# MCU_V3_1.net
KiCad netlist of a schematic drawn in Altium Designer
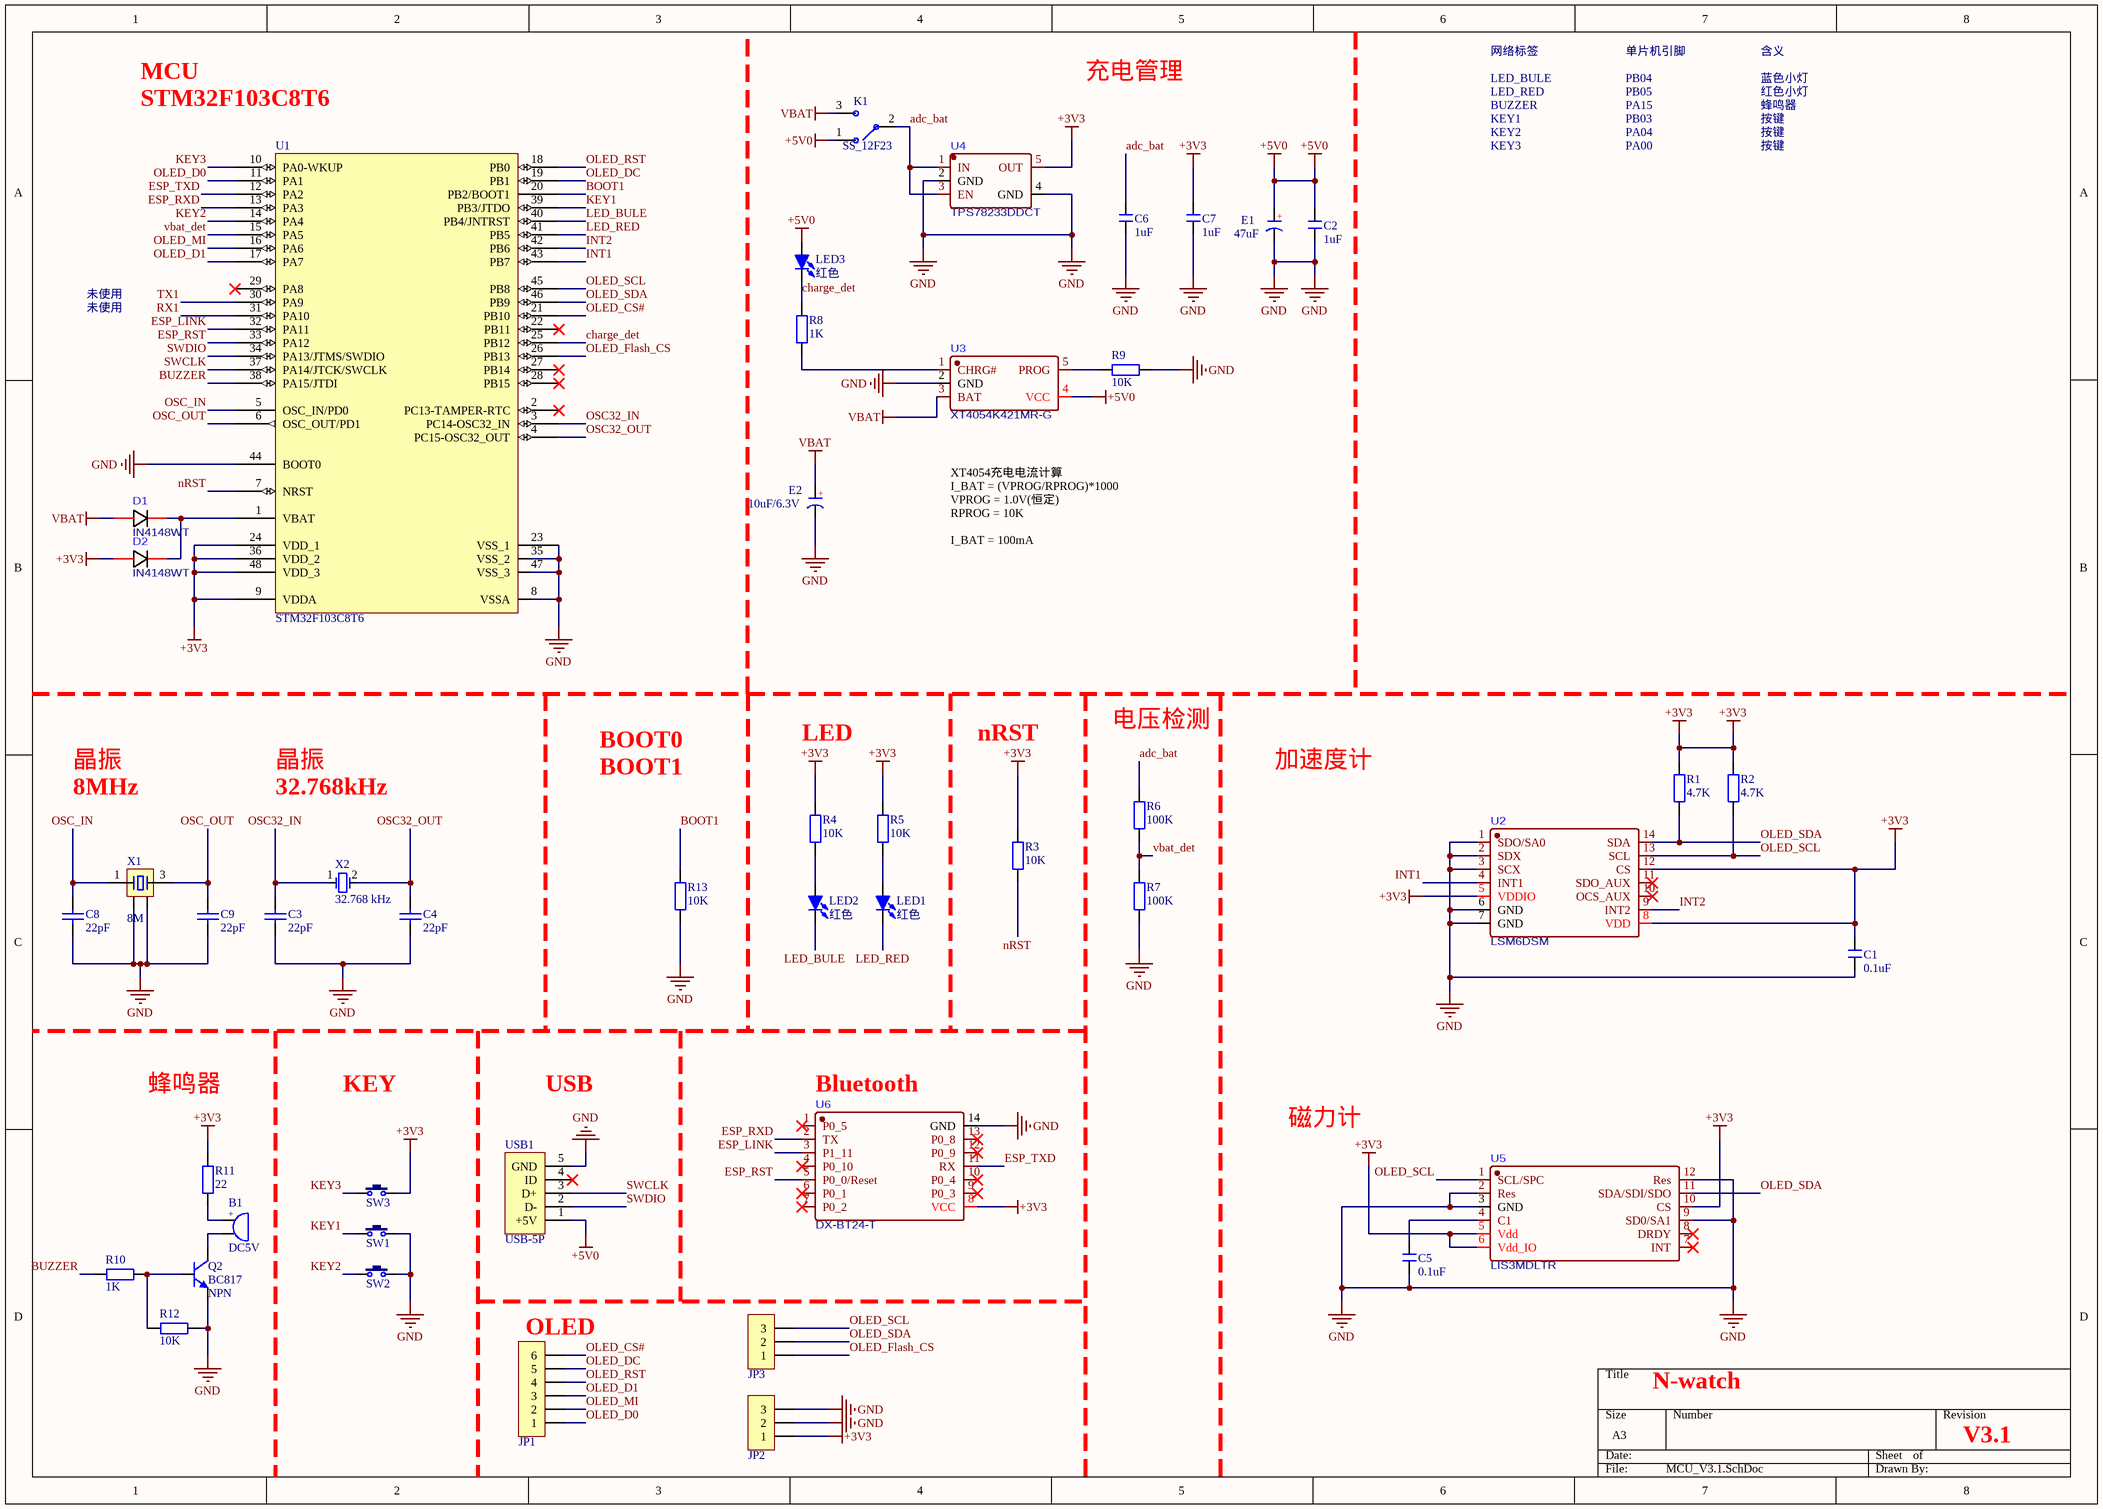
[diagram p0: MCU_V3.1.SchDoc]

(export (version "E")
  (design (tool "Eeschema 10.0.6"))
  (components
    (comp (ref "B1")
      (value "DC5V")
      (footprint "蜂鸣器5020")
      (description "蜂鸣器")
      (fields (field (name "版权归属") "黎明电子style"))
      (libsource (lib "未分类器件") (part "BEEP"))
    )
    (comp (ref "C1")
      (value "0.1uF")
      (footprint "C 0603")
      (description "无极性贴片电容")
      (fields (field (name "版权归属") "黎明电子style"))
      (libsource (lib "电阻-电容-电感") (part "C"))
    )
    (comp (ref "C2")
      (value "1uF")
      (footprint "C 0603")
      (description "无极性贴片电容")
      (fields (field (name "版权归属") "黎明电子style"))
      (libsource (lib "电阻-电容-电感") (part "C"))
    )
    (comp (ref "C3")
      (value "22pF")
      (footprint "C 0603")
      (description "贴片电容/MLCC电容")
      (libsource (lib "") (part "C_1"))
    )
    (comp (ref "C4")
      (value "22pF")
      (footprint "C 0603")
      (description "贴片电容/MLCC电容")
      (libsource (lib "") (part "C_1"))
    )
    (comp (ref "C5")
      (value "0.1uF")
      (footprint "C 0603")
      (description "无极性贴片电容")
      (fields (field (name "版权归属") "黎明电子style"))
      (libsource (lib "电阻-电容-电感") (part "C"))
    )
    (comp (ref "C6")
      (value "1uF")
      (footprint "C 0603")
      (description "无极性贴片电容")
      (fields (field (name "版权归属") "黎明电子style"))
      (libsource (lib "电阻-电容-电感") (part "C"))
    )
    (comp (ref "C7")
      (value "1uF")
      (footprint "C 0603")
      (description "无极性贴片电容")
      (fields (field (name "版权归属") "黎明电子style"))
      (libsource (lib "电阻-电容-电感") (part "C"))
    )
    (comp (ref "C8")
      (value "22pF")
      (footprint "C 0603")
      (description "贴片电容/MLCC电容")
      (libsource (lib "R-L-C-FUSE-XTAL-FB-RX") (part "C"))
    )
    (comp (ref "C9")
      (value "22pF")
      (footprint "C 0603")
      (description "贴片电容/MLCC电容")
      (libsource (lib "R-L-C-FUSE-XTAL-FB-RX") (part "C"))
    )
    (comp (ref "D1") (value "IN4148WT") (footprint "IN4148WT") (libsource (lib "Schlib1") (part "IN4148WT")))
    (comp (ref "D2") (value "IN4148WT") (footprint "IN4148WT") (libsource (lib "Schlib1") (part "IN4148WT")))
    (comp (ref "E1")
      (value "47uF")
      (footprint "CD A(3216)")
      (description "贴片钽电容")
      (fields (field (name "版权归属") "黎明电子style"))
      (libsource (lib "电阻-电容-电感") (part "C-CD"))
    )
    (comp (ref "E2")
      (value "10uF/6.3V")
      (footprint "CD A(3216)")
      (description "贴片钽电容")
      (fields (field (name "版权归属") "黎明电子style"))
      (libsource (lib "电阻-电容-电感") (part "C-CD"))
    )
    (comp (ref "JP1")
      (value "HDR-1X6")
      (footprint "HDR-1X6")
      (description "6P接插件")
      (fields (field (name "版权归属") "黎明电子style"))
      (libsource (lib "接插件") (part "Header 6"))
    )
    (comp (ref "JP2")
      (value "HDR-1X3")
      (footprint "OLED_3PIN")
      (description "3P接插件")
      (fields (field (name "版权归属") "黎明电子style"))
      (libsource (lib "接插件") (part "Header 3"))
    )
    (comp (ref "JP3")
      (value "HDR-1X3")
      (footprint "OLED_3PIN")
      (description "3P接插件")
      (fields (field (name "版权归属") "黎明电子style"))
      (libsource (lib "接插件") (part "Header 3"))
    )
    (comp (ref "K1") (value "SS_12F23") (footprint "SS_12F23") (libsource (lib "Schlib1") (part "SS_12F23")))
    (comp (ref "LED1")
      (value "红色")
      (footprint "LED 0603G")
      (description "贴片LED")
      (fields (field (name "版权归属") "黎明电子style"))
      (libsource (lib "LED") (part "LED-SMD"))
    )
    (comp (ref "LED2")
      (value "红色")
      (footprint "LED 0603G")
      (description "贴片LED")
      (fields (field (name "版权归属") "黎明电子style"))
      (libsource (lib "LED") (part "LED-SMD"))
    )
    (comp (ref "LED3")
      (value "红色")
      (footprint "LED 0603G")
      (description "贴片LED")
      (fields (field (name "版权归属") "黎明电子style"))
      (libsource (lib "LED") (part "LED-SMD"))
    )
    (comp (ref "Q2")
      (value "BC817")
      (footprint "SOT23-3N")
      (description "高频放大-NPN型")
      (fields (field (name "版权归属") "黎明电子style"))
      (libsource (lib "三极管") (part "8050-SMD"))
    )
    (comp (ref "R1")
      (value "4.7K")
      (footprint "R0603_M")
      (description "贴片电阻")
      (libsource (lib "R-L-C-FUSE-XTAL-FB-RX") (part "R"))
    )
    (comp (ref "R2")
      (value "4.7K")
      (footprint "R0603_M")
      (description "贴片电阻")
      (libsource (lib "R-L-C-FUSE-XTAL-FB-RX") (part "R"))
    )
    (comp (ref "R3")
      (value "10K")
      (footprint "R0603_M")
      (description "贴片电阻")
      (libsource (lib "R-L-C-FUSE-XTAL-FB-RX") (part "R"))
    )
    (comp (ref "R4")
      (value "10K")
      (footprint "R0603_M")
      (description "贴片电阻")
      (libsource (lib "R-L-C-FUSE-XTAL-FB-RX") (part "R"))
    )
    (comp (ref "R5")
      (value "10K")
      (footprint "R0603_M")
      (description "贴片电阻")
      (libsource (lib "R-L-C-FUSE-XTAL-FB-RX") (part "R"))
    )
    (comp (ref "R6")
      (value "100K")
      (footprint "R0603_M")
      (description "贴片电阻")
      (libsource (lib "R-L-C-FUSE-XTAL-FB-RX") (part "R"))
    )
    (comp (ref "R7")
      (value "100K")
      (footprint "R0603_M")
      (description "贴片电阻")
      (libsource (lib "R-L-C-FUSE-XTAL-FB-RX") (part "R"))
    )
    (comp (ref "R8")
      (value "1K")
      (footprint "R0603_M")
      (description "贴片电阻")
      (libsource (lib "R-L-C-FUSE-XTAL-FB-RX") (part "R"))
    )
    (comp (ref "R9")
      (value "10K")
      (footprint "R0603_M")
      (description "贴片电阻")
      (libsource (lib "R-L-C-FUSE-XTAL-FB-RX") (part "R"))
    )
    (comp (ref "R10")
      (value "1K")
      (footprint "R0603_M")
      (description "贴片电阻")
      (libsource (lib "R-L-C-FUSE-XTAL-FB-RX") (part "R"))
    )
    (comp (ref "R11")
      (value "22")
      (footprint "R0603_M")
      (description "贴片电阻")
      (libsource (lib "R-L-C-FUSE-XTAL-FB-RX") (part "R"))
    )
    (comp (ref "R12")
      (value "10K")
      (footprint "R0603_M")
      (description "贴片电阻")
      (libsource (lib "R-L-C-FUSE-XTAL-FB-RX") (part "R"))
    )
    (comp (ref "R13")
      (value "10K")
      (footprint "R0603_M")
      (description "贴片电阻")
      (libsource (lib "R-L-C-FUSE-XTAL-FB-RX") (part "R"))
    )
    (comp (ref "SW1")
      (value "3x6x5")
      (footprint "SB-2*4*3.5")
      (description "3x6轻触开关")
      (fields (field (name "版权归属") "黎明电子style"))
      (libsource (lib "按键-开关") (part "TSW 3x6"))
    )
    (comp (ref "SW2")
      (value "3x6x5")
      (footprint "SB-2*4*3.5")
      (description "3x6轻触开关")
      (fields (field (name "版权归属") "黎明电子style"))
      (libsource (lib "按键-开关") (part "TSW 3x6"))
    )
    (comp (ref "SW3")
      (value "3x6x5")
      (footprint "SB-2*4*3.5")
      (description "3x6轻触开关")
      (fields (field (name "版权归属") "黎明电子style"))
      (libsource (lib "按键-开关") (part "TSW 3x6"))
    )
    (comp (ref "U1")
      (value "STM32F103C8T6")
      (footprint "LQFP48 7X7_N")
      (description "Flaah:64/RAM:20/IO:36")
      (fields (field (name "版权归属") "黎明电子style"))
      (libsource (lib "STM32系列单片机") (part "STM32F103C8T6"))
    )
    (comp (ref "U2") (value "LSM6DSM") (footprint "LSM6DSM") (libsource (lib "Schlib1") (part "LSM6DSM")))
    (comp (ref "U3")
      (value "XT4054K421MR-G")
      (footprint "SOT-23-5_L3.0-W1.7-P0.95-LS2.8-BR")
      (libsource (lib "Schlib1") (part "XT4054K421MR-G"))
    )
    (comp (ref "U4")
      (value "TPS78233DDCT")
      (footprint "SOT-23-5_L3.0-W1.7-P0.95-LS2.8-BR")
      (libsource (lib "Schlib1") (part "TPS78233DDCT"))
    )
    (comp (ref "U5")
      (value "LIS3MDLTR")
      (footprint "LIS3MDLTR")
      (libsource (lib "Schlib1") (part "LIS3MDLTR"))
    )
    (comp (ref "U6")
      (value "DX-BT24-T")
      (footprint "DX-BT24-T")
      (libsource (lib "Schlib1") (part "DX-BT24-T"))
    )
    (comp (ref "USB1")
      (value "USB-5P")
      (footprint "MICRO-USB")
      (description "微型USB母座")
      (fields (field (name "版权归属") "黎明电子style"))
      (libsource (lib "接口类") (part "USB-5P"))
    )
    (comp (ref "X1")
      (value "8M")
      (footprint "XTAL-3225")
      (description "4脚晶振")
      (fields (field (name "版权归属") "源创客"))
      (libsource (lib "Schlib1") (part "XTAL-4"))
    )
    (comp (ref "X2")
      (value "32.768 kHz")
      (footprint "XTAL-3215")
      (description "Crystal Oscillator")
      (fields (field (name "PUBLISHER") "Altium Limited"))
      (libsource (lib "Schlib1") (part "XTAL"))
    )
  )
  (nets
    (net (code "1") (name "+3V3") (class "Default")
      (node (ref "C1") (pin "2") (pinfunction "2_2") (pintype "passive"))
      (node (ref "C7") (pin "2") (pinfunction "2_2") (pintype "passive"))
      (node (ref "D2") (pin "1") (pinfunction "1_1") (pintype "passive"))
      (node (ref "JP2") (pin "1") (pinfunction "1_1") (pintype "passive"))
      (node (ref "R1") (pin "2") (pinfunction "2_2") (pintype "passive"))
      (node (ref "R11") (pin "2") (pinfunction "2_2") (pintype "passive"))
      (node (ref "R2") (pin "2") (pinfunction "2_2") (pintype "passive"))
      (node (ref "R3") (pin "2") (pinfunction "2_2") (pintype "passive"))
      (node (ref "R4") (pin "2") (pinfunction "2_2") (pintype "passive"))
      (node (ref "R5") (pin "2") (pinfunction "2_2") (pintype "passive"))
      (node (ref "SW3") (pin "2") (pinfunction "2_2") (pintype "passive"))
      (node (ref "U1") (pin "24") (pinfunction "VDD_1_24") (pintype "power_in"))
      (node (ref "U1") (pin "36") (pinfunction "VDD_2_36") (pintype "power_in"))
      (node (ref "U1") (pin "48") (pinfunction "VDD_3_48") (pintype "power_in"))
      (node (ref "U1") (pin "9") (pinfunction "VDDA_9") (pintype "power_in"))
      (node (ref "U2") (pin "12") (pinfunction "CS_12") (pintype "passive"))
      (node (ref "U2") (pin "5") (pinfunction "VDDIO_5") (pintype "passive"))
      (node (ref "U2") (pin "8") (pinfunction "VDD_8") (pintype "passive"))
      (node (ref "U4") (pin "5") (pinfunction "OUT_5") (pintype "passive"))
      (node (ref "U5") (pin "10") (pinfunction "CS_10") (pintype "passive"))
      (node (ref "U5") (pin "5") (pinfunction "Vdd_5") (pintype "passive"))
      (node (ref "U5") (pin "6") (pinfunction "Vdd_IO_6") (pintype "passive"))
      (node (ref "U6") (pin "8") (pinfunction "VCC_8") (pintype "passive"))
    )
    (net (code "2") (name "+5V0") (class "Default")
      (node (ref "C2") (pin "2") (pinfunction "2_2") (pintype "passive"))
      (node (ref "E1") (pin "1") (pinfunction "A_1") (pintype "passive"))
      (node (ref "K1") (pin "1") (pinfunction "1_1") (pintype "passive"))
      (node (ref "LED3") (pin "1") (pinfunction "A_1") (pintype "passive"))
      (node (ref "U3") (pin "4") (pinfunction "VCC_4") (pintype "passive"))
      (node (ref "USB1") (pin "1") (pinfunction "+5V_1") (pintype "passive"))
    )
    (net (code "4") (name "/BOOT1") (class "Default")
      (node (ref "R13") (pin "2") (pinfunction "2_2") (pintype "passive"))
      (node (ref "U1") (pin "20") (pinfunction "PB2/BOOT1_20") (pintype "passive"))
    )
    (net (code "5") (name "/BUZZER") (class "Default")
      (node (ref "R10") (pin "2") (pinfunction "2_2") (pintype "passive"))
      (node (ref "U1") (pin "38") (pinfunction "PA15/JTDI_38") (pintype "bidirectional"))
    )
    (net (code "6") (name "/ESP_LINK") (class "Default")
      (node (ref "U1") (pin "32") (pinfunction "PA11_32") (pintype "bidirectional"))
      (node (ref "U6") (pin "3") (pinfunction "P1_11_3") (pintype "passive"))
    )
    (net (code "7") (name "/ESP_RST") (class "Default")
      (node (ref "U1") (pin "33") (pinfunction "PA12_33") (pintype "bidirectional"))
      (node (ref "U6") (pin "5") (pinfunction "P0_0/Reset_5") (pintype "passive"))
    )
    (net (code "8") (name "/ESP_RXD") (class "Default")
      (node (ref "U1") (pin "13") (pinfunction "PA3_13") (pintype "bidirectional"))
      (node (ref "U6") (pin "2") (pinfunction "TX_2") (pintype "passive"))
    )
    (net (code "9") (name "/ESP_TXD") (class "Default")
      (node (ref "U1") (pin "12") (pinfunction "PA2_12") (pintype "bidirectional"))
      (node (ref "U6") (pin "11") (pinfunction "RX_11") (pintype "passive"))
    )
    (net (code "10") (name "/INT1") (class "Default")
      (node (ref "U1") (pin "43") (pinfunction "PB7_43") (pintype "bidirectional"))
      (node (ref "U2") (pin "4") (pinfunction "INT1_4") (pintype "passive"))
    )
    (net (code "11") (name "/INT2") (class "Default")
      (node (ref "U1") (pin "42") (pinfunction "PB6_42") (pintype "bidirectional"))
      (node (ref "U2") (pin "9") (pinfunction "INT2_9") (pintype "passive"))
    )
    (net (code "12") (name "/KEY1") (class "Default")
      (node (ref "SW1") (pin "1") (pinfunction "1_1") (pintype "passive"))
      (node (ref "U1") (pin "39") (pinfunction "PB3/JTDO_39") (pintype "bidirectional"))
    )
    (net (code "13") (name "/KEY2") (class "Default")
      (node (ref "SW2") (pin "1") (pinfunction "1_1") (pintype "passive"))
      (node (ref "U1") (pin "14") (pinfunction "PA4_14") (pintype "bidirectional"))
    )
    (net (code "14") (name "/KEY3") (class "Default")
      (node (ref "SW3") (pin "1") (pinfunction "1_1") (pintype "passive"))
      (node (ref "U1") (pin "10") (pinfunction "PA0-WKUP_10") (pintype "bidirectional"))
    )
    (net (code "15") (name "/LED_BULE") (class "Default")
      (node (ref "LED2") (pin "2") (pinfunction "K_2") (pintype "passive"))
      (node (ref "U1") (pin "40") (pinfunction "PB4/JNTRST_40") (pintype "bidirectional"))
    )
    (net (code "16") (name "/LED_RED") (class "Default")
      (node (ref "LED1") (pin "2") (pinfunction "K_2") (pintype "passive"))
      (node (ref "U1") (pin "41") (pinfunction "PB5_41") (pintype "bidirectional"))
    )
    (net (code "17") (name "/OLED_CS#") (class "Default")
      (node (ref "JP1") (pin "6") (pinfunction "6_6") (pintype "passive"))
      (node (ref "U1") (pin "21") (pinfunction "PB10_21") (pintype "bidirectional"))
    )
    (net (code "18") (name "/OLED_D0") (class "Default")
      (node (ref "JP1") (pin "1") (pinfunction "1_1") (pintype "passive"))
      (node (ref "U1") (pin "11") (pinfunction "PA1_11") (pintype "bidirectional"))
    )
    (net (code "19") (name "/OLED_D1") (class "Default")
      (node (ref "JP1") (pin "3") (pinfunction "3_3") (pintype "passive"))
      (node (ref "U1") (pin "17") (pinfunction "PA7_17") (pintype "bidirectional"))
    )
    (net (code "20") (name "/OLED_DC") (class "Default")
      (node (ref "JP1") (pin "5") (pinfunction "5_5") (pintype "passive"))
      (node (ref "U1") (pin "19") (pinfunction "PB1_19") (pintype "bidirectional"))
    )
    (net (code "21") (name "/OLED_Flash_CS") (class "Default")
      (node (ref "JP3") (pin "1") (pinfunction "1_1") (pintype "passive"))
      (node (ref "U1") (pin "26") (pinfunction "PB13_26") (pintype "bidirectional"))
    )
    (net (code "22") (name "/OLED_MI") (class "Default")
      (node (ref "JP1") (pin "2") (pinfunction "2_2") (pintype "passive"))
      (node (ref "U1") (pin "16") (pinfunction "PA6_16") (pintype "bidirectional"))
    )
    (net (code "23") (name "/OLED_RST") (class "Default")
      (node (ref "JP1") (pin "4") (pinfunction "4_4") (pintype "passive"))
      (node (ref "U1") (pin "18") (pinfunction "PB0_18") (pintype "bidirectional"))
    )
    (net (code "24") (name "/OLED_SCL") (class "Default")
      (node (ref "JP3") (pin "3") (pinfunction "3_3") (pintype "passive"))
      (node (ref "R2") (pin "1") (pinfunction "1_1") (pintype "passive"))
      (node (ref "U1") (pin "45") (pinfunction "PB8_45") (pintype "bidirectional"))
      (node (ref "U2") (pin "13") (pinfunction "SCL_13") (pintype "passive"))
      (node (ref "U5") (pin "1") (pinfunction "SCL/SPC_1") (pintype "passive"))
    )
    (net (code "25") (name "/OLED_SDA") (class "Default")
      (node (ref "JP3") (pin "2") (pinfunction "2_2") (pintype "passive"))
      (node (ref "R1") (pin "1") (pinfunction "1_1") (pintype "passive"))
      (node (ref "U1") (pin "46") (pinfunction "PB9_46") (pintype "bidirectional"))
      (node (ref "U2") (pin "14") (pinfunction "SDA_14") (pintype "passive"))
      (node (ref "U5") (pin "11") (pinfunction "SDA/SDI/SDO_11") (pintype "passive"))
    )
    (net (code "26") (name "/OSC32_IN") (class "Default")
      (node (ref "C3") (pin "1") (pinfunction "1_1") (pintype "passive"))
      (node (ref "U1") (pin "3") (pinfunction "PC14-OSC32_IN_3") (pintype "bidirectional"))
      (node (ref "X2") (pin "1") (pinfunction "OSC1_1") (pintype "passive"))
    )
    (net (code "27") (name "/OSC32_OUT") (class "Default")
      (node (ref "C4") (pin "1") (pinfunction "1_1") (pintype "passive"))
      (node (ref "U1") (pin "4") (pinfunction "PC15-OSC32_OUT_4") (pintype "bidirectional"))
      (node (ref "X2") (pin "2") (pinfunction "OSC2_2") (pintype "passive"))
    )
    (net (code "28") (name "/OSC_IN") (class "Default")
      (node (ref "C8") (pin "2") (pinfunction "2_2") (pintype "passive"))
      (node (ref "U1") (pin "5") (pinfunction "OSC_IN/PD0_5") (pintype "passive"))
      (node (ref "X1") (pin "1") (pinfunction "1_1") (pintype "passive"))
    )
    (net (code "29") (name "/OSC_OUT") (class "Default")
      (node (ref "C9") (pin "2") (pinfunction "2_2") (pintype "passive"))
      (node (ref "U1") (pin "6") (pinfunction "OSC_OUT/PD1_6") (pintype "output"))
      (node (ref "X1") (pin "3") (pinfunction "3_3") (pintype "passive"))
    )
    (net (code "30") (name "/RX1") (class "Default")
      (node (ref "U1") (pin "31") (pinfunction "PA10_31") (pintype "bidirectional"))
    )
    (net (code "31") (name "/SWCLK") (class "Default")
      (node (ref "U1") (pin "37") (pinfunction "PA14/JTCK/SWCLK_37") (pintype "bidirectional"))
      (node (ref "USB1") (pin "3") (pinfunction "D+_3") (pintype "passive"))
    )
    (net (code "32") (name "/SWDIO") (class "Default")
      (node (ref "U1") (pin "34") (pinfunction "PA13/JTMS/SWDIO_34") (pintype "bidirectional"))
      (node (ref "USB1") (pin "2") (pinfunction "D-_2") (pintype "passive"))
    )
    (net (code "33") (name "/TX1") (class "Default")
      (node (ref "U1") (pin "30") (pinfunction "PA9_30") (pintype "bidirectional"))
    )
    (net (code "34") (name "/adc_bat") (class "Default")
      (node (ref "C6") (pin "2") (pinfunction "2_2") (pintype "passive"))
      (node (ref "K1") (pin "2") (pinfunction "2_2") (pintype "passive"))
      (node (ref "R6") (pin "2") (pinfunction "2_2") (pintype "passive"))
      (node (ref "U4") (pin "1") (pinfunction "IN_1") (pintype "passive"))
      (node (ref "U4") (pin "3") (pinfunction "EN_3") (pintype "passive"))
    )
    (net (code "35") (name "/charge_det") (class "Default")
      (node (ref "LED3") (pin "2") (pinfunction "K_2") (pintype "passive"))
      (node (ref "R8") (pin "2") (pinfunction "2_2") (pintype "passive"))
      (node (ref "U1") (pin "25") (pinfunction "PB12_25") (pintype "bidirectional"))
    )
    (net (code "36") (name "/nRST") (class "Default")
      (node (ref "R3") (pin "1") (pinfunction "1_1") (pintype "passive"))
      (node (ref "U1") (pin "7") (pinfunction "NRST_7") (pintype "bidirectional"))
    )
    (net (code "37") (name "/vbat_det") (class "Default")
      (node (ref "R6") (pin "1") (pinfunction "1_1") (pintype "passive"))
      (node (ref "R7") (pin "2") (pinfunction "2_2") (pintype "passive"))
      (node (ref "U1") (pin "15") (pinfunction "PA5_15") (pintype "bidirectional"))
    )
    (net (code "38") (name "GND") (class "Default")
      (node (ref "C1") (pin "1") (pinfunction "1_1") (pintype "passive"))
      (node (ref "C2") (pin "1") (pinfunction "1_1") (pintype "passive"))
      (node (ref "C3") (pin "2") (pinfunction "2_2") (pintype "passive"))
      (node (ref "C4") (pin "2") (pinfunction "2_2") (pintype "passive"))
      (node (ref "C5") (pin "1") (pinfunction "1_1") (pintype "passive"))
      (node (ref "C6") (pin "1") (pinfunction "1_1") (pintype "passive"))
      (node (ref "C7") (pin "1") (pinfunction "1_1") (pintype "passive"))
      (node (ref "C8") (pin "1") (pinfunction "1_1") (pintype "passive"))
      (node (ref "C9") (pin "1") (pinfunction "1_1") (pintype "passive"))
      (node (ref "E1") (pin "2") (pinfunction "K_2") (pintype "passive"))
      (node (ref "E2") (pin "2") (pinfunction "K_2") (pintype "passive"))
      (node (ref "JP2") (pin "2") (pinfunction "2_2") (pintype "passive"))
      (node (ref "JP2") (pin "3") (pinfunction "3_3") (pintype "passive"))
      (node (ref "Q2") (pin "2") (pinfunction "E_2") (pintype "passive"))
      (node (ref "R12") (pin "1") (pinfunction "1_1") (pintype "passive"))
      (node (ref "R13") (pin "1") (pinfunction "1_1") (pintype "passive"))
      (node (ref "R7") (pin "1") (pinfunction "1_1") (pintype "passive"))
      (node (ref "R9") (pin "1") (pinfunction "1_1") (pintype "passive"))
      (node (ref "SW1") (pin "2") (pinfunction "2_2") (pintype "passive"))
      (node (ref "SW2") (pin "2") (pinfunction "2_2") (pintype "passive"))
      (node (ref "U1") (pin "23") (pinfunction "VSS_1_23") (pintype "power_in"))
      (node (ref "U1") (pin "35") (pinfunction "VSS_2_35") (pintype "power_in"))
      (node (ref "U1") (pin "44") (pinfunction "BOOT0_44") (pintype "passive"))
      (node (ref "U1") (pin "47") (pinfunction "VSS_3_47") (pintype "power_in"))
      (node (ref "U1") (pin "8") (pinfunction "VSSA_8") (pintype "power_in"))
      (node (ref "U2") (pin "1") (pinfunction "SDO/SA0_1") (pintype "passive"))
      (node (ref "U2") (pin "2") (pinfunction "SDX_2") (pintype "passive"))
      (node (ref "U2") (pin "3") (pinfunction "SCX_3") (pintype "passive"))
      (node (ref "U2") (pin "6") (pinfunction "GND_6") (pintype "passive"))
      (node (ref "U2") (pin "7") (pinfunction "GND_7") (pintype "passive"))
      (node (ref "U3") (pin "2") (pinfunction "GND_2") (pintype "passive"))
      (node (ref "U4") (pin "2") (pinfunction "GND_2") (pintype "passive"))
      (node (ref "U4") (pin "4") (pinfunction "GND_4") (pintype "passive"))
      (node (ref "U5") (pin "12") (pinfunction "Res_12") (pintype "passive"))
      (node (ref "U5") (pin "2") (pinfunction "Res_2") (pintype "passive"))
      (node (ref "U5") (pin "3") (pinfunction "GND_3") (pintype "passive"))
      (node (ref "U5") (pin "9") (pinfunction "SD0/SA1_9") (pintype "passive"))
      (node (ref "U6") (pin "14") (pinfunction "GND_14") (pintype "passive"))
      (node (ref "USB1") (pin "5") (pinfunction "GND_5") (pintype "passive"))
      (node (ref "X1") (pin "2") (pinfunction "2_2") (pintype "passive"))
      (node (ref "X1") (pin "4") (pinfunction "4_4") (pintype "passive"))
    )
    (net (code "39") (name "Net-(B1-Pad1)") (class "Default")
      (node (ref "B1") (pin "1") (pinfunction "1_1") (pintype "passive"))
      (node (ref "R11") (pin "1") (pinfunction "1_1") (pintype "passive"))
    )
    (net (code "40") (name "Net-(LED1-A)") (class "Default")
      (node (ref "LED1") (pin "1") (pinfunction "A_1") (pintype "passive"))
      (node (ref "R5") (pin "1") (pinfunction "1_1") (pintype "passive"))
    )
    (net (code "41") (name "Net-(LED2-A)") (class "Default")
      (node (ref "LED2") (pin "1") (pinfunction "A_1") (pintype "passive"))
      (node (ref "R4") (pin "1") (pinfunction "1_1") (pintype "passive"))
    )
    (net (code "42") (name "Net-(Q2-B)") (class "Default")
      (node (ref "Q2") (pin "1") (pinfunction "B_1") (pintype "passive"))
      (node (ref "R10") (pin "1") (pinfunction "1_1") (pintype "passive"))
      (node (ref "R12") (pin "2") (pinfunction "2_2") (pintype "passive"))
    )
    (net (code "43") (name "Net-(Q2-C)") (class "Default")
      (node (ref "B1") (pin "2") (pinfunction "2_2") (pintype "passive"))
      (node (ref "Q2") (pin "3") (pinfunction "C_3") (pintype "passive"))
    )
    (net (code "44") (name "Net-(U1-VBAT)") (class "Default")
      (node (ref "D1") (pin "2") (pinfunction "2_2") (pintype "passive"))
      (node (ref "D2") (pin "2") (pinfunction "2_2") (pintype "passive"))
      (node (ref "U1") (pin "1") (pinfunction "VBAT_1") (pintype "power_in"))
    )
    (net (code "45") (name "Net-(U3-CHRG#)") (class "Default")
      (node (ref "R8") (pin "1") (pinfunction "1_1") (pintype "passive"))
      (node (ref "U3") (pin "1") (pinfunction "CHRG#_1") (pintype "passive"))
    )
    (net (code "46") (name "Net-(U3-PROG)") (class "Default")
      (node (ref "R9") (pin "2") (pinfunction "2_2") (pintype "passive"))
      (node (ref "U3") (pin "5") (pinfunction "PROG_5") (pintype "passive"))
    )
    (net (code "47") (name "Net-(U5-C1)") (class "Default")
      (node (ref "C5") (pin "2") (pinfunction "2_2") (pintype "passive"))
      (node (ref "U5") (pin "4") (pinfunction "C1_4") (pintype "passive"))
    )
    (net (code "48") (name "VBAT") (class "Default")
      (node (ref "D1") (pin "1") (pinfunction "1_1") (pintype "passive"))
      (node (ref "E2") (pin "1") (pinfunction "A_1") (pintype "passive"))
      (node (ref "K1") (pin "3") (pinfunction "3_3") (pintype "passive"))
      (node (ref "U3") (pin "3") (pinfunction "BAT_3") (pintype "passive"))
    )
    (net (code "49") (name "unconnected-(U1-PA8-Pad29)") (class "Default")
      (node (ref "U1") (pin "29") (pinfunction "PA8_29") (pintype "bidirectional+no_connect"))
    )
    (net (code "50") (name "unconnected-(U1-PB11-Pad22)") (class "Default")
      (node (ref "U1") (pin "22") (pinfunction "PB11_22") (pintype "bidirectional+no_connect"))
    )
    (net (code "51") (name "unconnected-(U1-PB14-Pad27)") (class "Default")
      (node (ref "U1") (pin "27") (pinfunction "PB14_27") (pintype "bidirectional+no_connect"))
    )
    (net (code "52") (name "unconnected-(U1-PB15-Pad28)") (class "Default")
      (node (ref "U1") (pin "28") (pinfunction "PB15_28") (pintype "bidirectional+no_connect"))
    )
    (net (code "53") (name "unconnected-(U1-PC13-TAMPER-RTC-Pad2)") (class "Default")
      (node (ref "U1") (pin "2") (pinfunction "PC13-TAMPER-RTC_2") (pintype "bidirectional+no_connect"))
    )
    (net (code "54") (name "unconnected-(U2-OCS_AUX-Pad10)") (class "Default")
      (node (ref "U2") (pin "10") (pinfunction "OCS_AUX_10") (pintype "passive+no_connect"))
    )
    (net (code "55") (name "unconnected-(U2-SDO_AUX-Pad11)") (class "Default")
      (node (ref "U2") (pin "11") (pinfunction "SDO_AUX_11") (pintype "passive+no_connect"))
    )
    (net (code "56") (name "unconnected-(U5-DRDY-Pad8)") (class "Default")
      (node (ref "U5") (pin "8") (pinfunction "DRDY_8") (pintype "passive+no_connect"))
    )
    (net (code "57") (name "unconnected-(U5-INT-Pad7)") (class "Default")
      (node (ref "U5") (pin "7") (pinfunction "INT_7") (pintype "passive+no_connect"))
    )
    (net (code "58") (name "unconnected-(U6-P0_1-Pad6)") (class "Default")
      (node (ref "U6") (pin "6") (pinfunction "P0_1_6") (pintype "passive+no_connect"))
    )
    (net (code "59") (name "unconnected-(U6-P0_2-Pad7)") (class "Default")
      (node (ref "U6") (pin "7") (pinfunction "P0_2_7") (pintype "passive+no_connect"))
    )
    (net (code "60") (name "unconnected-(U6-P0_3-Pad9)") (class "Default")
      (node (ref "U6") (pin "9") (pinfunction "P0_3_9") (pintype "passive+no_connect"))
    )
    (net (code "61") (name "unconnected-(U6-P0_4-Pad10)") (class "Default")
      (node (ref "U6") (pin "10") (pinfunction "P0_4_10") (pintype "passive+no_connect"))
    )
    (net (code "62") (name "unconnected-(U6-P0_5-Pad1)") (class "Default")
      (node (ref "U6") (pin "1") (pinfunction "P0_5_1") (pintype "passive+no_connect"))
    )
    (net (code "63") (name "unconnected-(U6-P0_8-Pad13)") (class "Default")
      (node (ref "U6") (pin "13") (pinfunction "P0_8_13") (pintype "passive+no_connect"))
    )
    (net (code "64") (name "unconnected-(U6-P0_9-Pad12)") (class "Default")
      (node (ref "U6") (pin "12") (pinfunction "P0_9_12") (pintype "passive+no_connect"))
    )
    (net (code "65") (name "unconnected-(U6-P0_10-Pad4)") (class "Default")
      (node (ref "U6") (pin "4") (pinfunction "P0_10_4") (pintype "passive+no_connect"))
    )
    (net (code "66") (name "unconnected-(USB1-ID-Pad4)") (class "Default")
      (node (ref "USB1") (pin "4") (pinfunction "ID_4") (pintype "passive+no_connect"))
    )
  )
)
